# detector_full.net
KiCad netlist of a schematic drawn in EAGLE
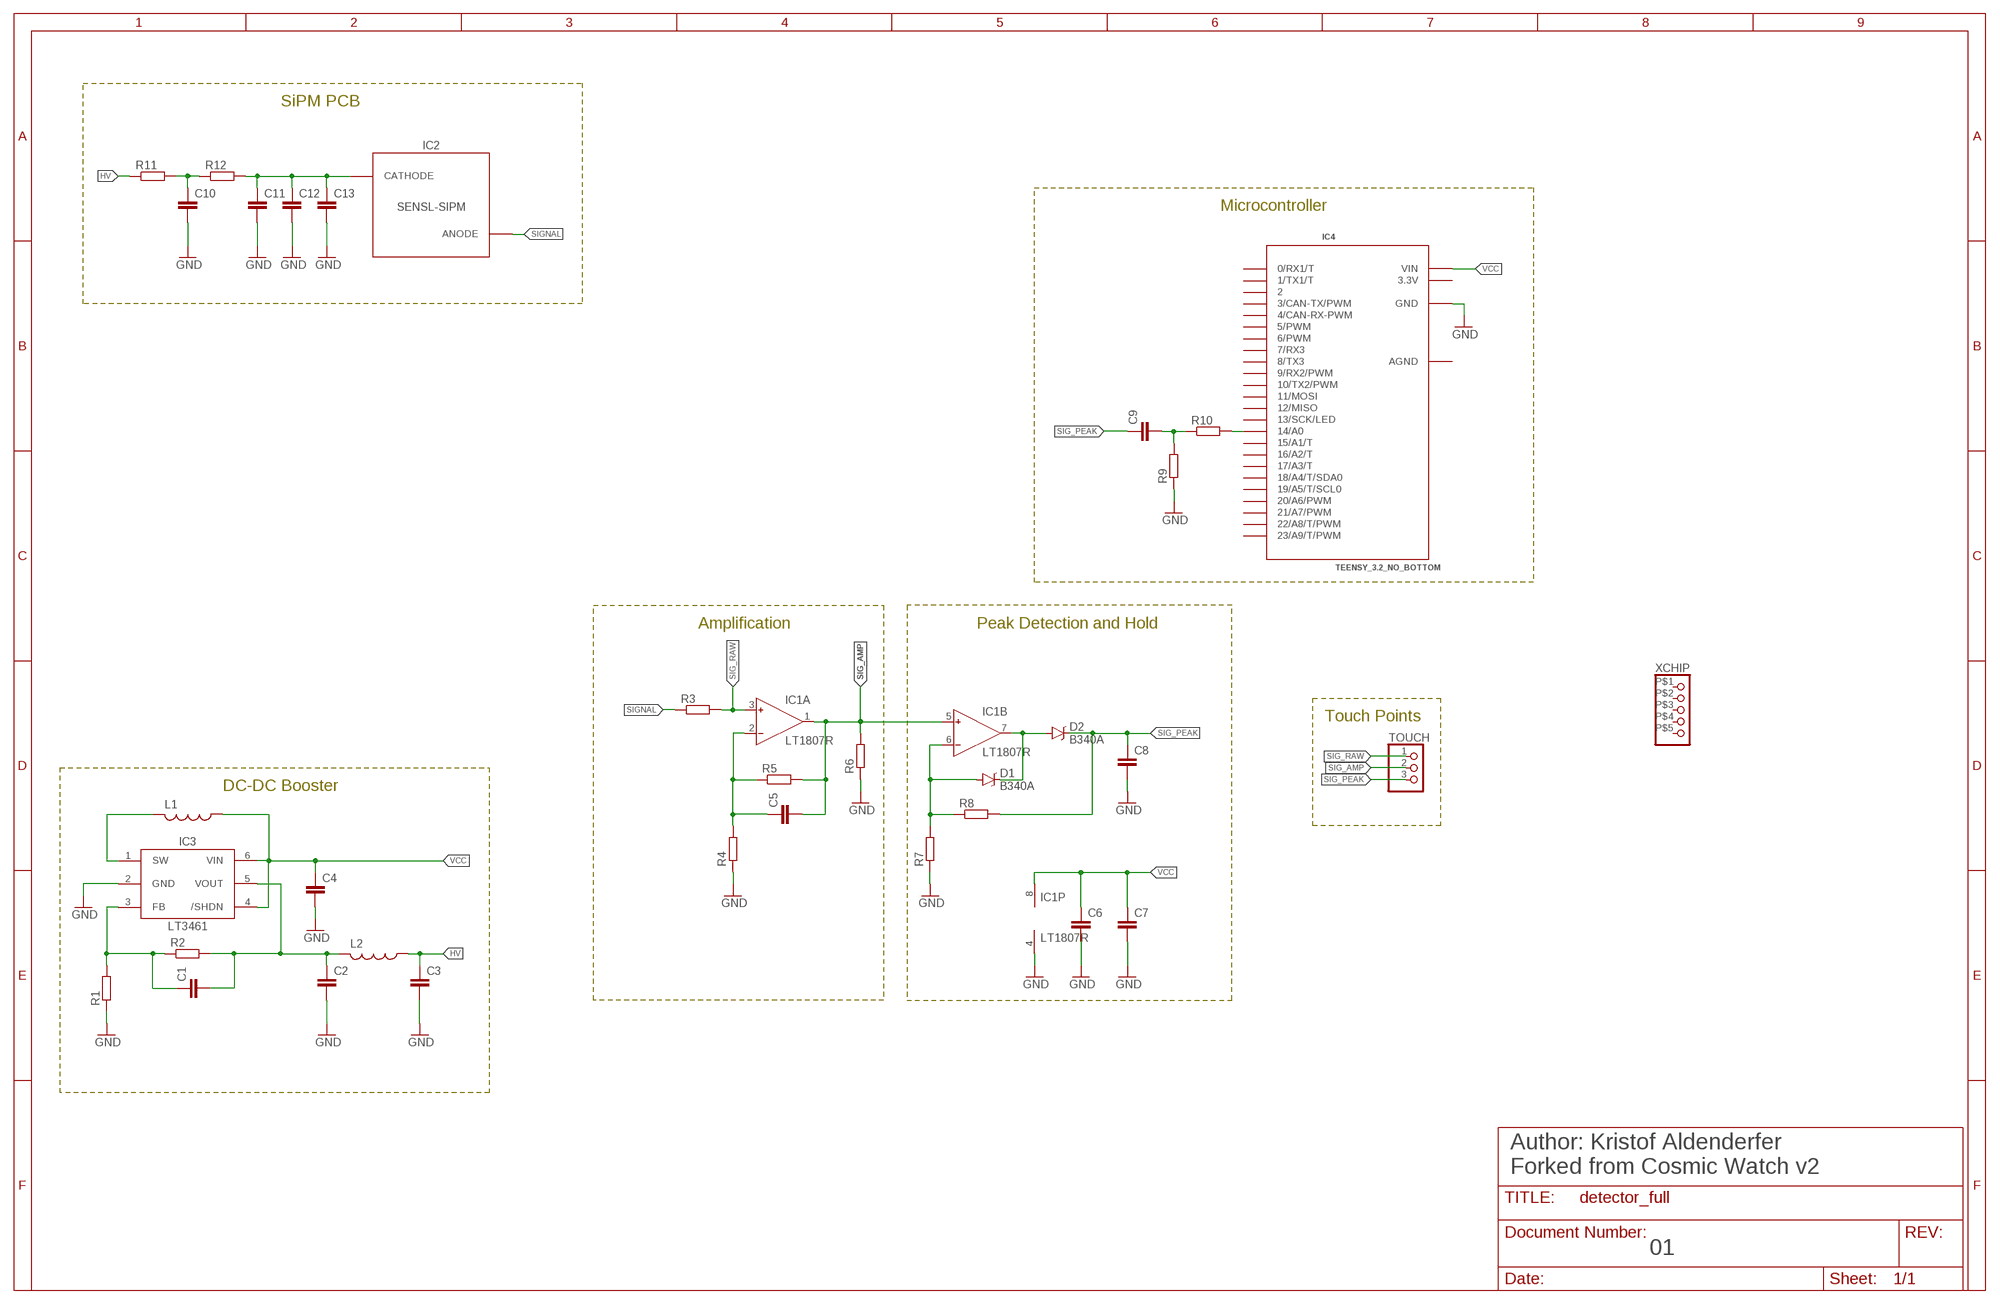
[diagram p0: schematic, sheet 1]

(export (version "E")
  (design (tool "Eeschema 10.0.6"))
  (components
    (comp (ref "C1")
      (value "C-EUC0805K")
      (footprint "eagle-import:C0805K")
      (libsource (lib "eagle-import") (part "C-EUC0805K"))
    )
    (comp (ref "C2")
      (value "C-EUC0805K")
      (footprint "eagle-import:C0805K")
      (libsource (lib "eagle-import") (part "C-EUC0805K"))
    )
    (comp (ref "C3")
      (value "C-EUC0805K")
      (footprint "eagle-import:C0805K")
      (libsource (lib "eagle-import") (part "C-EUC0805K"))
    )
    (comp (ref "C4")
      (value "C-EUC0805K")
      (footprint "eagle-import:C0805K")
      (libsource (lib "eagle-import") (part "C-EUC0805K"))
    )
    (comp (ref "C5")
      (value "C-EUC0805K")
      (footprint "eagle-import:C0805K")
      (libsource (lib "eagle-import") (part "C-EUC0805K"))
    )
    (comp (ref "C6")
      (value "C-EUC0805K")
      (footprint "eagle-import:C0805K")
      (libsource (lib "eagle-import") (part "C-EUC0805K"))
    )
    (comp (ref "C7")
      (value "C-EUC0805K")
      (footprint "eagle-import:C0805K")
      (libsource (lib "eagle-import") (part "C-EUC0805K"))
    )
    (comp (ref "C8")
      (value "C-EUC0805K")
      (footprint "eagle-import:C0805K")
      (libsource (lib "eagle-import") (part "C-EUC0805K"))
    )
    (comp (ref "C9")
      (value "C-EUC0805K")
      (footprint "eagle-import:C0805K")
      (libsource (lib "eagle-import") (part "C-EUC0805K"))
    )
    (comp (ref "C10")
      (value "C-EUC0805K")
      (footprint "eagle-import:C0805K")
      (libsource (lib "eagle-import") (part "C-EUC0805K"))
    )
    (comp (ref "C11")
      (value "C-EUC0805K")
      (footprint "eagle-import:C0805K")
      (libsource (lib "eagle-import") (part "C-EUC0805K"))
    )
    (comp (ref "C12")
      (value "C-EUC0805K")
      (footprint "eagle-import:C0805K")
      (libsource (lib "eagle-import") (part "C-EUC0805K"))
    )
    (comp (ref "C13")
      (value "C-EUC0805K")
      (footprint "eagle-import:C0805K")
      (libsource (lib "eagle-import") (part "C-EUC0805K"))
    )
    (comp (ref "D1")
      (value "B340A")
      (footprint "eagle-import:SMA-DIODE")
      (libsource (lib "eagle-import") (part "DIODE-SCHOTTKY-B340A"))
    )
    (comp (ref "D2")
      (value "B340A")
      (footprint "eagle-import:SMA-DIODE")
      (libsource (lib "eagle-import") (part "DIODE-SCHOTTKY-B340A"))
    )
    (comp (ref "IC1")
      (value "LT1807R")
      (footprint "eagle-import:SO8")
      (fields (field (name "MF") "ALTERA CORPORATION") (field (name "MPN") "AD746JRZ"))
      (libsource (lib "eagle-import") (part "LT1807R"))
    )
    (comp (ref "IC2")
      (value "SENSL-SIPM")
      (footprint "eagle-import:MICROFC-60035")
      (libsource (lib "eagle-import") (part "SENSL-SIPM"))
    )
    (comp (ref "IC3")
      (value "LT3461")
      (footprint "eagle-import:SOT23-6")
      (libsource (lib "eagle-import") (part "LT3461"))
    )
    (comp (ref "IC4")
      (value "TEENSY_3.2_NO_BOTTOM")
      (footprint "eagle-import:TEENSY_3.2_NO_BOTTOM")
      (libsource (lib "eagle-import") (part "TEENSY_3.2_NO_BOTTOM"))
    )
    (comp (ref "L1")
      (value "L-USL2012C")
      (footprint "eagle-import:L2012C")
      (libsource (lib "eagle-import") (part "L-USL2012C"))
    )
    (comp (ref "L2")
      (value "L-USL2012C")
      (footprint "eagle-import:L2012C")
      (libsource (lib "eagle-import") (part "L-USL2012C"))
    )
    (comp (ref "R1")
      (value "R-EU_M0805")
      (footprint "eagle-import:M0805")
      (libsource (lib "eagle-import") (part "R-EU_M0805"))
    )
    (comp (ref "R2")
      (value "R-EU_M0805")
      (footprint "eagle-import:M0805")
      (libsource (lib "eagle-import") (part "R-EU_M0805"))
    )
    (comp (ref "R3")
      (value "R-EU_M0805")
      (footprint "eagle-import:M0805")
      (libsource (lib "eagle-import") (part "R-EU_M0805"))
    )
    (comp (ref "R4")
      (value "R-EU_M0805")
      (footprint "eagle-import:M0805")
      (libsource (lib "eagle-import") (part "R-EU_M0805"))
    )
    (comp (ref "R5")
      (value "R-EU_M0805")
      (footprint "eagle-import:M0805")
      (libsource (lib "eagle-import") (part "R-EU_M0805"))
    )
    (comp (ref "R6")
      (value "R-EU_M0805")
      (footprint "eagle-import:M0805")
      (libsource (lib "eagle-import") (part "R-EU_M0805"))
    )
    (comp (ref "R7")
      (value "R-EU_M0805")
      (footprint "eagle-import:M0805")
      (libsource (lib "eagle-import") (part "R-EU_M0805"))
    )
    (comp (ref "R8")
      (value "R-EU_M0805")
      (footprint "eagle-import:M0805")
      (libsource (lib "eagle-import") (part "R-EU_M0805"))
    )
    (comp (ref "R9")
      (value "R-EU_M0805")
      (footprint "eagle-import:M0805")
      (libsource (lib "eagle-import") (part "R-EU_M0805"))
    )
    (comp (ref "R10")
      (value "R-EU_M0805")
      (footprint "eagle-import:M0805")
      (libsource (lib "eagle-import") (part "R-EU_M0805"))
    )
    (comp (ref "R11")
      (value "R-EU_M0805")
      (footprint "eagle-import:M0805")
      (libsource (lib "eagle-import") (part "R-EU_M0805"))
    )
    (comp (ref "R12")
      (value "R-EU_M0805")
      (footprint "eagle-import:M0805")
      (libsource (lib "eagle-import") (part "R-EU_M0805"))
    )
    (comp (ref "TOUCH")
      (value "PINHD-1X3")
      (footprint "eagle-import:1X03")
      (libsource (lib "eagle-import") (part "PINHD-1X3"))
    )
    (comp (ref "XCHIP")
      (value "XCHIP-1X5")
      (footprint "eagle-import:1X05_PAD")
      (libsource (lib "eagle-import") (part "XCHIP-1X5"))
    )
  )
  (nets
    (net (code "1") (name "/3.3V") (class "Default")
      (node (ref "IC4") (pin "3.3V") (pinfunction "3.3V_3.3V") (pintype "power_in"))
    )
    (net (code "2") (name "/AGND") (class "Default")
      (node (ref "IC4") (pin "AGND") (pinfunction "AGND_AGND") (pintype "power_in"))
    )
    (net (code "3") (name "GND") (class "Default")
      (node (ref "C10") (pin "2") (pinfunction "2_2") (pintype "passive"))
      (node (ref "C11") (pin "2") (pinfunction "2_2") (pintype "passive"))
      (node (ref "C12") (pin "2") (pinfunction "2_2") (pintype "passive"))
      (node (ref "C13") (pin "2") (pinfunction "2_2") (pintype "passive"))
      (node (ref "C2") (pin "2") (pinfunction "2_2") (pintype "passive"))
      (node (ref "C3") (pin "2") (pinfunction "2_2") (pintype "passive"))
      (node (ref "C4") (pin "2") (pinfunction "2_2") (pintype "passive"))
      (node (ref "C6") (pin "2") (pinfunction "2_2") (pintype "passive"))
      (node (ref "C7") (pin "2") (pinfunction "2_2") (pintype "passive"))
      (node (ref "C8") (pin "2") (pinfunction "2_2") (pintype "passive"))
      (node (ref "IC1") (pin "4") (pinfunction "V-_4") (pintype "power_in"))
      (node (ref "IC3") (pin "2") (pinfunction "GND_2") (pintype "power_in"))
      (node (ref "IC4") (pin "GND") (pinfunction "GND_GND") (pintype "power_in"))
      (node (ref "R1") (pin "1") (pinfunction "1_1") (pintype "passive"))
      (node (ref "R4") (pin "1") (pinfunction "1_1") (pintype "passive"))
      (node (ref "R6") (pin "1") (pinfunction "1_1") (pintype "passive"))
      (node (ref "R7") (pin "1") (pinfunction "1_1") (pintype "passive"))
      (node (ref "R9") (pin "1") (pinfunction "1_1") (pintype "passive"))
    )
    (net (code "4") (name "HV") (class "Default")
      (node (ref "C3") (pin "1") (pinfunction "1_1") (pintype "passive"))
      (node (ref "L2") (pin "1") (pinfunction "1_1") (pintype "passive"))
      (node (ref "R11") (pin "1") (pinfunction "1_1") (pintype "passive"))
    )
    (net (code "5") (name "Net-(C9-Pad2)") (class "Default")
      (node (ref "C9") (pin "2") (pinfunction "2_2") (pintype "passive"))
      (node (ref "R10") (pin "1") (pinfunction "1_1") (pintype "passive"))
      (node (ref "R9") (pin "2") (pinfunction "2_2") (pintype "passive"))
    )
    (net (code "6") (name "Net-(C10-Pad1)") (class "Default")
      (node (ref "C10") (pin "1") (pinfunction "1_1") (pintype "passive"))
      (node (ref "R11") (pin "2") (pinfunction "2_2") (pintype "passive"))
      (node (ref "R12") (pin "1") (pinfunction "1_1") (pintype "passive"))
    )
    (net (code "7") (name "Net-(C11-Pad1)") (class "Default")
      (node (ref "C11") (pin "1") (pinfunction "1_1") (pintype "passive"))
      (node (ref "C12") (pin "1") (pinfunction "1_1") (pintype "passive"))
      (node (ref "C13") (pin "1") (pinfunction "1_1") (pintype "passive"))
      (node (ref "IC2") (pin "CATHODE") (pinfunction "CATHODE_CATHODE") (pintype "bidirectional"))
      (node (ref "R12") (pin "2") (pinfunction "2_2") (pintype "passive"))
    )
    (net (code "8") (name "Net-(IC1A-IN-)") (class "Default")
      (node (ref "C5") (pin "1") (pinfunction "1_1") (pintype "passive"))
      (node (ref "IC1") (pin "2") (pinfunction "IN-_2") (pintype "input"))
      (node (ref "R4") (pin "2") (pinfunction "2_2") (pintype "passive"))
      (node (ref "R5") (pin "1") (pinfunction "1_1") (pintype "passive"))
    )
    (net (code "9") (name "Net-(IC1B-IN-)") (class "Default")
      (node (ref "D1") (pin "A") (pinfunction "A_A") (pintype "passive"))
      (node (ref "IC1") (pin "6") (pinfunction "IN-_6") (pintype "input"))
      (node (ref "R7") (pin "2") (pinfunction "2_2") (pintype "passive"))
      (node (ref "R8") (pin "1") (pinfunction "1_1") (pintype "passive"))
    )
    (net (code "10") (name "Net-(IC1B-OUT)") (class "Default")
      (node (ref "D1") (pin "C") (pinfunction "C_C") (pintype "passive"))
      (node (ref "D2") (pin "A") (pinfunction "A_A") (pintype "passive"))
      (node (ref "IC1") (pin "7") (pinfunction "OUT_7") (pintype "output"))
    )
    (net (code "11") (name "Net-(IC3-FB)") (class "Default")
      (node (ref "C1") (pin "1") (pinfunction "1_1") (pintype "passive"))
      (node (ref "IC3") (pin "3") (pinfunction "FB_3") (pintype "input"))
      (node (ref "R1") (pin "2") (pinfunction "2_2") (pintype "passive"))
      (node (ref "R2") (pin "1") (pinfunction "1_1") (pintype "passive"))
    )
    (net (code "12") (name "Net-(IC3-SW)") (class "Default")
      (node (ref "IC3") (pin "1") (pinfunction "SW_1") (pintype "output"))
      (node (ref "L1") (pin "2") (pinfunction "2_2") (pintype "passive"))
    )
    (net (code "13") (name "Net-(IC3-VOUT)") (class "Default")
      (node (ref "C1") (pin "2") (pinfunction "2_2") (pintype "passive"))
      (node (ref "C2") (pin "1") (pinfunction "1_1") (pintype "passive"))
      (node (ref "IC3") (pin "5") (pinfunction "VOUT_5") (pintype "output"))
      (node (ref "L2") (pin "2") (pinfunction "2_2") (pintype "passive"))
      (node (ref "R2") (pin "2") (pinfunction "2_2") (pintype "passive"))
    )
    (net (code "14") (name "Net-(IC4-Pad14{slash}A0)") (class "Default")
      (node (ref "IC4") (pin "14/A0") (pinfunction "14/A0_14/A0") (pintype "bidirectional"))
      (node (ref "R10") (pin "2") (pinfunction "2_2") (pintype "passive"))
    )
    (net (code "15") (name "SIGNAL") (class "Default")
      (node (ref "IC2") (pin "ANODE") (pinfunction "ANODE_ANODE") (pintype "bidirectional"))
      (node (ref "R3") (pin "1") (pinfunction "1_1") (pintype "passive"))
    )
    (net (code "16") (name "SIG_AMP") (class "Default")
      (node (ref "C5") (pin "2") (pinfunction "2_2") (pintype "passive"))
      (node (ref "IC1") (pin "1") (pinfunction "OUT_1") (pintype "output"))
      (node (ref "IC1") (pin "5") (pinfunction "IN+_5") (pintype "input"))
      (node (ref "R5") (pin "2") (pinfunction "2_2") (pintype "passive"))
      (node (ref "R6") (pin "2") (pinfunction "2_2") (pintype "passive"))
      (node (ref "TOUCH") (pin "2") (pinfunction "2_2") (pintype "passive"))
    )
    (net (code "17") (name "SIG_PEAK") (class "Default")
      (node (ref "C8") (pin "1") (pinfunction "1_1") (pintype "passive"))
      (node (ref "C9") (pin "1") (pinfunction "1_1") (pintype "passive"))
      (node (ref "D2") (pin "C") (pinfunction "C_C") (pintype "passive"))
      (node (ref "R8") (pin "2") (pinfunction "2_2") (pintype "passive"))
      (node (ref "TOUCH") (pin "3") (pinfunction "3_3") (pintype "passive"))
    )
    (net (code "18") (name "SIG_RAW") (class "Default")
      (node (ref "IC1") (pin "3") (pinfunction "IN+_3") (pintype "input"))
      (node (ref "R3") (pin "2") (pinfunction "2_2") (pintype "passive"))
      (node (ref "TOUCH") (pin "1") (pinfunction "1_1") (pintype "passive"))
    )
    (net (code "19") (name "VCC") (class "Default")
      (node (ref "C4") (pin "1") (pinfunction "1_1") (pintype "passive"))
      (node (ref "C6") (pin "1") (pinfunction "1_1") (pintype "passive"))
      (node (ref "C7") (pin "1") (pinfunction "1_1") (pintype "passive"))
      (node (ref "IC1") (pin "8") (pinfunction "V+_8") (pintype "power_in"))
      (node (ref "IC3") (pin "4") (pinfunction "/SHDN_4") (pintype "input"))
      (node (ref "IC3") (pin "6") (pinfunction "VIN_6") (pintype "input"))
      (node (ref "IC4") (pin "VIN") (pinfunction "VIN_VIN") (pintype "power_in"))
      (node (ref "L1") (pin "1") (pinfunction "1_1") (pintype "passive"))
    )
    (net (code "20") (name "unconnected-(IC4-0{slash}RX1{slash}T-Pad0)") (class "Default")
      (node (ref "IC4") (pin "0") (pinfunction "0/RX1/T_0") (pintype "bidirectional"))
    )
    (net (code "21") (name "unconnected-(IC4-1{slash}TX1{slash}T-Pad1)") (class "Default")
      (node (ref "IC4") (pin "1") (pinfunction "1/TX1/T_1") (pintype "bidirectional"))
    )
    (net (code "22") (name "unconnected-(IC4-3{slash}CAN-TX{slash}PWM-Pad3)") (class "Default")
      (node (ref "IC4") (pin "3") (pinfunction "3/CAN-TX/PWM_3") (pintype "bidirectional"))
    )
    (net (code "23") (name "unconnected-(IC4-4{slash}CAN-RX-PWM-Pad4)") (class "Default")
      (node (ref "IC4") (pin "4") (pinfunction "4/CAN-RX-PWM_4") (pintype "bidirectional"))
    )
    (net (code "24") (name "unconnected-(IC4-5{slash}PWM-Pad5)") (class "Default")
      (node (ref "IC4") (pin "5") (pinfunction "5/PWM_5") (pintype "bidirectional"))
    )
    (net (code "25") (name "unconnected-(IC4-6{slash}PWM-Pad6)") (class "Default")
      (node (ref "IC4") (pin "6") (pinfunction "6/PWM_6") (pintype "bidirectional"))
    )
    (net (code "26") (name "unconnected-(IC4-7{slash}RX3-Pad7)") (class "Default")
      (node (ref "IC4") (pin "7") (pinfunction "7/RX3_7") (pintype "bidirectional"))
    )
    (net (code "27") (name "unconnected-(IC4-8{slash}TX3-Pad8)") (class "Default")
      (node (ref "IC4") (pin "8") (pinfunction "8/TX3_8") (pintype "bidirectional"))
    )
    (net (code "28") (name "unconnected-(IC4-9{slash}RX2{slash}PWM-Pad9)") (class "Default")
      (node (ref "IC4") (pin "9") (pinfunction "9/RX2/PWM_9") (pintype "bidirectional"))
    )
    (net (code "29") (name "unconnected-(IC4-10{slash}TX2{slash}PWM-Pad10)") (class "Default")
      (node (ref "IC4") (pin "10") (pinfunction "10/TX2/PWM_10") (pintype "bidirectional"))
    )
    (net (code "30") (name "unconnected-(IC4-11{slash}MOSI-Pad11)") (class "Default")
      (node (ref "IC4") (pin "11") (pinfunction "11/MOSI_11") (pintype "bidirectional"))
    )
    (net (code "31") (name "unconnected-(IC4-12{slash}MISO-Pad12)") (class "Default")
      (node (ref "IC4") (pin "12") (pinfunction "12/MISO_12") (pintype "bidirectional"))
    )
    (net (code "32") (name "unconnected-(IC4-13{slash}SCK{slash}LED-Pad13)") (class "Default")
      (node (ref "IC4") (pin "13") (pinfunction "13/SCK/LED_13") (pintype "bidirectional"))
    )
    (net (code "33") (name "unconnected-(IC4-15{slash}A1{slash}T-Pad15{slash}A1)") (class "Default")
      (node (ref "IC4") (pin "15/A1") (pinfunction "15/A1/T_15/A1") (pintype "bidirectional"))
    )
    (net (code "34") (name "unconnected-(IC4-16{slash}A2{slash}T-Pad16{slash}A2)") (class "Default")
      (node (ref "IC4") (pin "16/A2") (pinfunction "16/A2/T_16/A2") (pintype "bidirectional"))
    )
    (net (code "35") (name "unconnected-(IC4-17{slash}A3{slash}T-Pad17{slash}A3)") (class "Default")
      (node (ref "IC4") (pin "17/A3") (pinfunction "17/A3/T_17/A3") (pintype "bidirectional"))
    )
    (net (code "36") (name "unconnected-(IC4-18{slash}A4{slash}T{slash}SDA0-Pad18{slash}A4)") (class "Default")
      (node (ref "IC4") (pin "18/A4") (pinfunction "18/A4/T/SDA0_18/A4") (pintype "bidirectional"))
    )
    (net (code "37") (name "unconnected-(IC4-19{slash}A5{slash}T{slash}SCL0-Pad19{slash}A5)") (class "Default")
      (node (ref "IC4") (pin "19/A5") (pinfunction "19/A5/T/SCL0_19/A5") (pintype "bidirectional"))
    )
    (net (code "38") (name "unconnected-(IC4-20{slash}A6{slash}PWM-Pad20{slash}A6)") (class "Default")
      (node (ref "IC4") (pin "20/A6") (pinfunction "20/A6/PWM_20/A6") (pintype "bidirectional"))
    )
    (net (code "39") (name "unconnected-(IC4-21{slash}A7{slash}PWM-Pad21{slash}A7)") (class "Default")
      (node (ref "IC4") (pin "21/A7") (pinfunction "21/A7/PWM_21/A7") (pintype "bidirectional"))
    )
    (net (code "40") (name "unconnected-(IC4-22{slash}A8{slash}T{slash}PWM-Pad22{slash}A8)") (class "Default")
      (node (ref "IC4") (pin "22/A8") (pinfunction "22/A8/T/PWM_22/A8") (pintype "bidirectional"))
    )
    (net (code "41") (name "unconnected-(IC4-23{slash}A9{slash}T{slash}PWM-Pad23{slash}A9)") (class "Default")
      (node (ref "IC4") (pin "23/A9") (pinfunction "23/A9/T/PWM_23/A9") (pintype "bidirectional"))
    )
    (net (code "42") (name "unconnected-(IC4-Pad2)") (class "Default")
      (node (ref "IC4") (pin "2") (pinfunction "2_2") (pintype "bidirectional"))
    )
    (net (code "43") (name "unconnected-(XCHIP-1-PadP$1)") (class "Default")
      (node (ref "XCHIP") (pin "P$1") (pinfunction "1_P$1") (pintype "passive"))
    )
    (net (code "44") (name "unconnected-(XCHIP-2-PadP$2)") (class "Default")
      (node (ref "XCHIP") (pin "P$2") (pinfunction "2_P$2") (pintype "passive"))
    )
    (net (code "45") (name "unconnected-(XCHIP-3-PadP$3)") (class "Default")
      (node (ref "XCHIP") (pin "P$3") (pinfunction "3_P$3") (pintype "passive"))
    )
    (net (code "46") (name "unconnected-(XCHIP-4-PadP$4)") (class "Default")
      (node (ref "XCHIP") (pin "P$4") (pinfunction "4_P$4") (pintype "passive"))
    )
    (net (code "47") (name "unconnected-(XCHIP-5-PadP$5)") (class "Default")
      (node (ref "XCHIP") (pin "P$5") (pinfunction "5_P$5") (pintype "passive"))
    )
  )
)
